# adv_timer.net
KiCad netlist of a schematic drawn in EAGLE
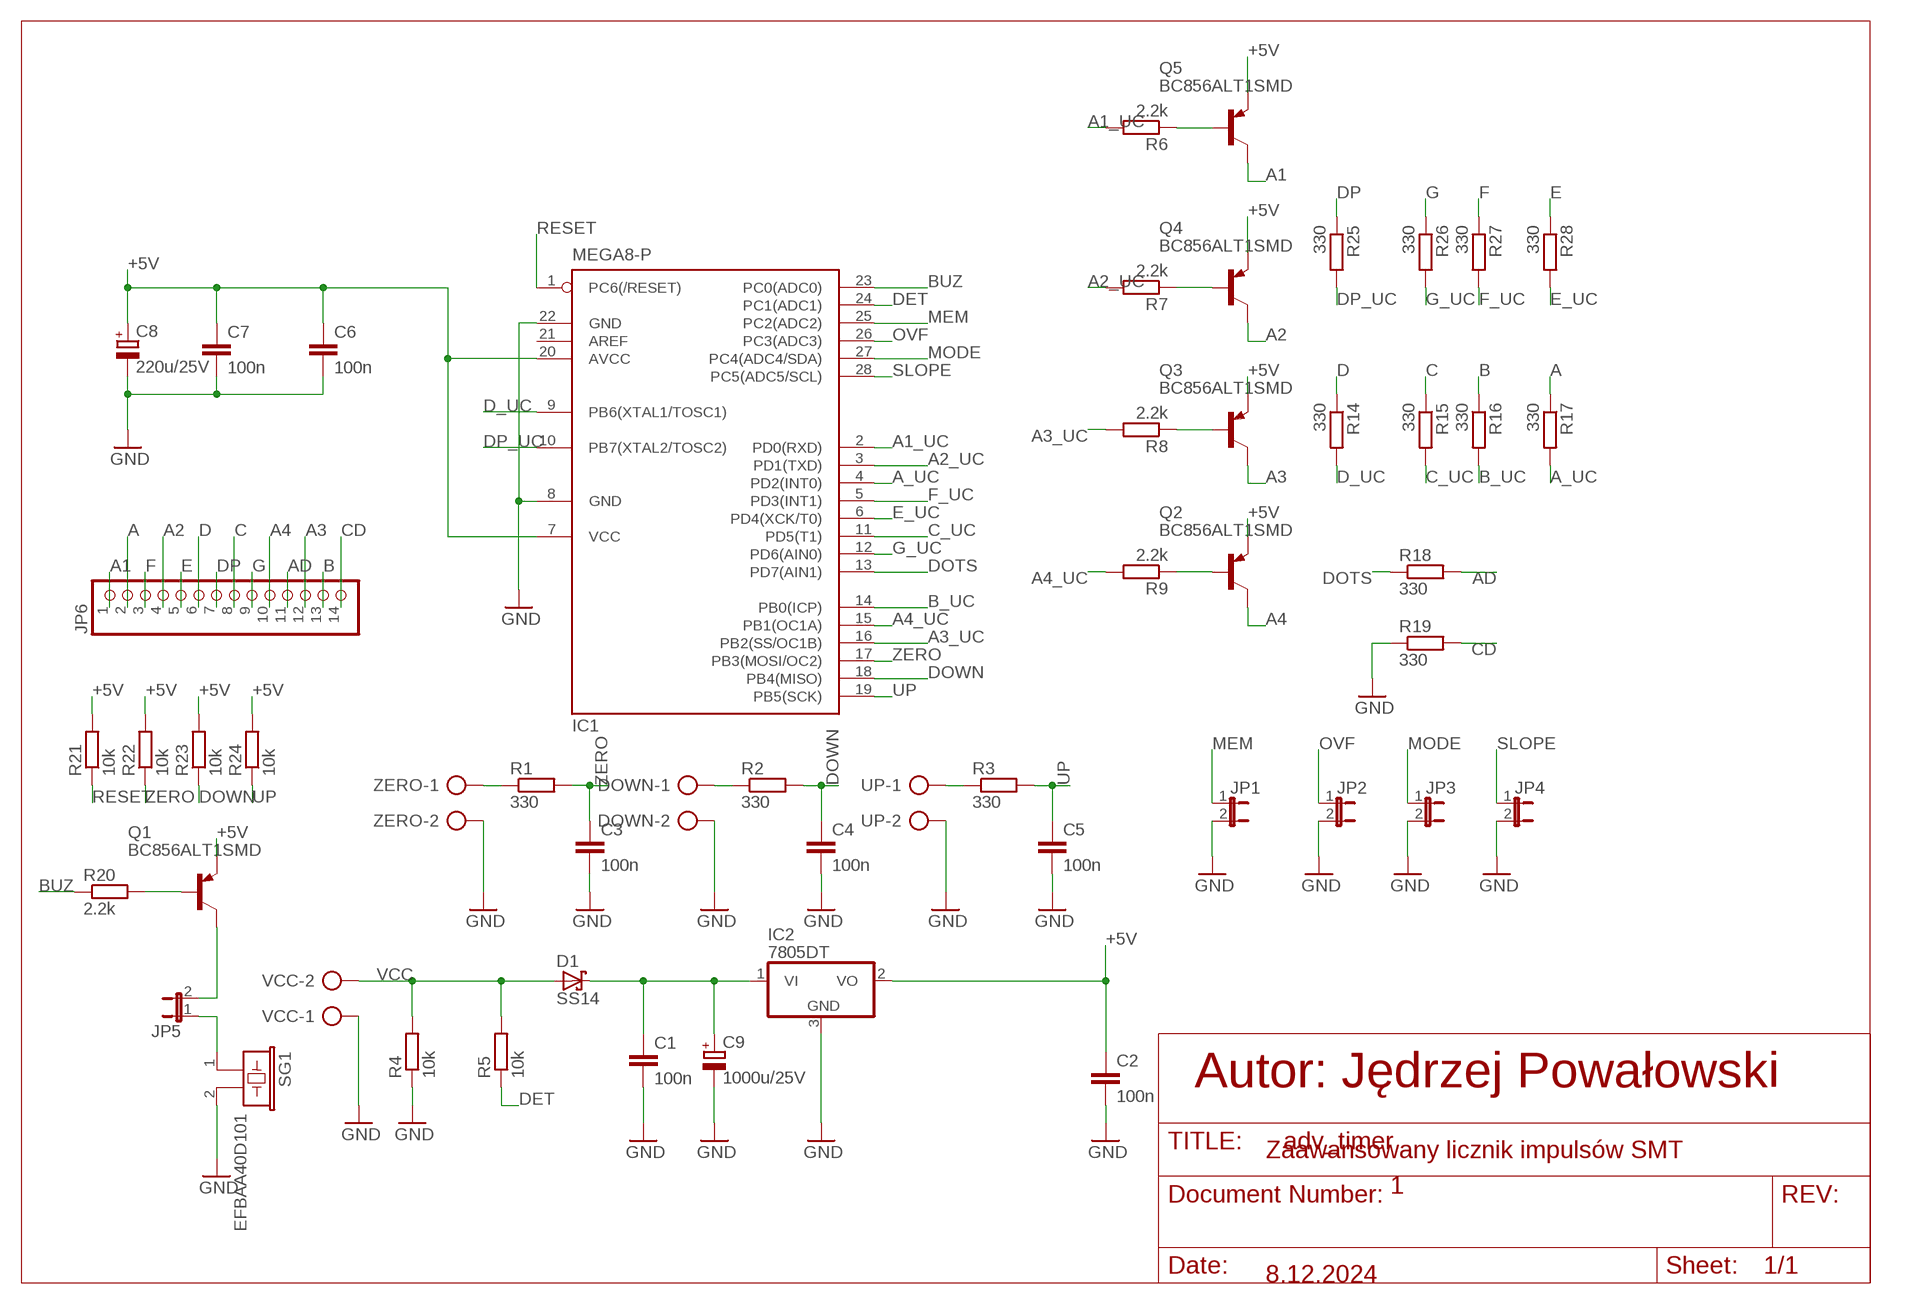
[diagram p0: schematic, sheet 1]

(export (version "E")
  (design (tool "Eeschema 10.0.6"))
  (components
    (comp (ref "C1")
      (value "100n")
      (footprint "eagle-import:C1210K")
      (libsource (lib "eagle-import") (part "C-EUC1210K"))
    )
    (comp (ref "C2")
      (value "100n")
      (footprint "eagle-import:C1210K")
      (libsource (lib "eagle-import") (part "C-EUC1210K"))
    )
    (comp (ref "C3")
      (value "100n")
      (footprint "eagle-import:C1210K")
      (libsource (lib "eagle-import") (part "C-EUC1210K"))
    )
    (comp (ref "C4")
      (value "100n")
      (footprint "eagle-import:C1210K")
      (libsource (lib "eagle-import") (part "C-EUC1210K"))
    )
    (comp (ref "C5")
      (value "100n")
      (footprint "eagle-import:C1210K")
      (libsource (lib "eagle-import") (part "C-EUC1210K"))
    )
    (comp (ref "C6")
      (value "100n")
      (footprint "eagle-import:C1210K")
      (libsource (lib "eagle-import") (part "C-EUC1210K"))
    )
    (comp (ref "C7")
      (value "100n")
      (footprint "eagle-import:C1210K")
      (libsource (lib "eagle-import") (part "C-EUC1210K"))
    )
    (comp (ref "C8")
      (value "220u/25V")
      (footprint "eagle-import:153CLV-0810")
      (libsource (lib "eagle-import") (part "CPOL-EU153CLV-0810"))
    )
    (comp (ref "C9")
      (value "1000u/25V")
      (footprint "eagle-import:153CLV-0810")
      (libsource (lib "eagle-import") (part "CPOL-EU153CLV-0810"))
    )
    (comp (ref "D1")
      (value "SS14")
      (footprint "eagle-import:DO-214AC")
      (fields (field (name "MF") "onsemi"))
      (libsource (lib "eagle-import") (part "SS14"))
    )
    (comp (ref "DOWN")
      (value "AK300/2")
      (footprint "eagle-import:AK300_2")
      (libsource (lib "eagle-import") (part "AK300/2"))
    )
    (comp (ref "IC1")
      (value "MEGA8-P")
      (footprint "eagle-import:DIL28-3")
      (libsource (lib "eagle-import") (part "MEGA8-P"))
    )
    (comp (ref "IC2")
      (value "7805DT")
      (footprint "eagle-import:TO252")
      (libsource (lib "eagle-import") (part "78DT05"))
    )
    (comp (ref "JP1")
      (value "JP1E")
      (footprint "eagle-import:JP1")
      (libsource (lib "eagle-import") (part "JP1E"))
    )
    (comp (ref "JP2")
      (value "JP1E")
      (footprint "eagle-import:JP1")
      (libsource (lib "eagle-import") (part "JP1E"))
    )
    (comp (ref "JP3")
      (value "JP1E")
      (footprint "eagle-import:JP1")
      (libsource (lib "eagle-import") (part "JP1E"))
    )
    (comp (ref "JP4")
      (value "JP1E")
      (footprint "eagle-import:JP1")
      (libsource (lib "eagle-import") (part "JP1E"))
    )
    (comp (ref "JP5")
      (value "JP1E")
      (footprint "eagle-import:JP1")
      (libsource (lib "eagle-import") (part "JP1E"))
    )
    (comp (ref "JP6")
      (value "PINHD-1X14/90")
      (footprint "eagle-import:1X14_90")
      (libsource (lib "eagle-import") (part "PINHD-1X14/90"))
    )
    (comp (ref "Q1")
      (value "BC856ALT1SMD")
      (footprint "eagle-import:SOT23-BEC")
      (libsource (lib "eagle-import") (part "BC856SMDALT1"))
    )
    (comp (ref "Q2")
      (value "BC856ALT1SMD")
      (footprint "eagle-import:SOT23-BEC")
      (libsource (lib "eagle-import") (part "BC856SMDALT1"))
    )
    (comp (ref "Q3")
      (value "BC856ALT1SMD")
      (footprint "eagle-import:SOT23-BEC")
      (libsource (lib "eagle-import") (part "BC856SMDALT1"))
    )
    (comp (ref "Q4")
      (value "BC856ALT1SMD")
      (footprint "eagle-import:SOT23-BEC")
      (libsource (lib "eagle-import") (part "BC856SMDALT1"))
    )
    (comp (ref "Q5")
      (value "BC856ALT1SMD")
      (footprint "eagle-import:SOT23-BEC")
      (libsource (lib "eagle-import") (part "BC856SMDALT1"))
    )
    (comp (ref "R1")
      (value "330")
      (footprint "eagle-import:M1206")
      (libsource (lib "eagle-import") (part "R-EU_M1206"))
    )
    (comp (ref "R2")
      (value "330")
      (footprint "eagle-import:M1206")
      (libsource (lib "eagle-import") (part "R-EU_M1206"))
    )
    (comp (ref "R3")
      (value "330")
      (footprint "eagle-import:M1206")
      (libsource (lib "eagle-import") (part "R-EU_M1206"))
    )
    (comp (ref "R4")
      (value "10k")
      (footprint "eagle-import:M1206")
      (libsource (lib "eagle-import") (part "R-EU_M1206"))
    )
    (comp (ref "R5")
      (value "10k")
      (footprint "eagle-import:M1206")
      (libsource (lib "eagle-import") (part "R-EU_M1206"))
    )
    (comp (ref "R6")
      (value "2.2k")
      (footprint "eagle-import:R0805")
      (libsource (lib "eagle-import") (part "R-EU_R0805"))
    )
    (comp (ref "R7")
      (value "2.2k")
      (footprint "eagle-import:R0805")
      (libsource (lib "eagle-import") (part "R-EU_R0805"))
    )
    (comp (ref "R8")
      (value "2.2k")
      (footprint "eagle-import:R0805")
      (libsource (lib "eagle-import") (part "R-EU_R0805"))
    )
    (comp (ref "R9")
      (value "2.2k")
      (footprint "eagle-import:R0805")
      (libsource (lib "eagle-import") (part "R-EU_R0805"))
    )
    (comp (ref "R14")
      (value "330")
      (footprint "eagle-import:R0805")
      (libsource (lib "eagle-import") (part "R-EU_R0805"))
    )
    (comp (ref "R15")
      (value "330")
      (footprint "eagle-import:R0805")
      (libsource (lib "eagle-import") (part "R-EU_R0805"))
    )
    (comp (ref "R16")
      (value "330")
      (footprint "eagle-import:R0805")
      (libsource (lib "eagle-import") (part "R-EU_R0805"))
    )
    (comp (ref "R17")
      (value "330")
      (footprint "eagle-import:R0805")
      (libsource (lib "eagle-import") (part "R-EU_R0805"))
    )
    (comp (ref "R18")
      (value "330")
      (footprint "eagle-import:R0805")
      (libsource (lib "eagle-import") (part "R-EU_R0805"))
    )
    (comp (ref "R19")
      (value "330")
      (footprint "eagle-import:R0805")
      (libsource (lib "eagle-import") (part "R-EU_R0805"))
    )
    (comp (ref "R20")
      (value "2.2k")
      (footprint "eagle-import:R0805")
      (libsource (lib "eagle-import") (part "R-EU_R0805"))
    )
    (comp (ref "R21")
      (value "10k")
      (footprint "eagle-import:R0805")
      (libsource (lib "eagle-import") (part "R-EU_R0805"))
    )
    (comp (ref "R22")
      (value "10k")
      (footprint "eagle-import:R0805")
      (libsource (lib "eagle-import") (part "R-EU_R0805"))
    )
    (comp (ref "R23")
      (value "10k")
      (footprint "eagle-import:R0805")
      (libsource (lib "eagle-import") (part "R-EU_R0805"))
    )
    (comp (ref "R24")
      (value "10k")
      (footprint "eagle-import:R0805")
      (libsource (lib "eagle-import") (part "R-EU_R0805"))
    )
    (comp (ref "R25")
      (value "330")
      (footprint "eagle-import:R0805")
      (libsource (lib "eagle-import") (part "R-EU_R0805"))
    )
    (comp (ref "R26")
      (value "330")
      (footprint "eagle-import:R0805")
      (libsource (lib "eagle-import") (part "R-EU_R0805"))
    )
    (comp (ref "R27")
      (value "330")
      (footprint "eagle-import:R0805")
      (libsource (lib "eagle-import") (part "R-EU_R0805"))
    )
    (comp (ref "R28")
      (value "330")
      (footprint "eagle-import:R0805")
      (libsource (lib "eagle-import") (part "R-EU_R0805"))
    )
    (comp (ref "SG1")
      (value "EFBAA40D101")
      (footprint "eagle-import:EFBAA40D101")
      (libsource (lib "eagle-import") (part "EFB?AA40D101"))
    )
    (comp (ref "UP")
      (value "AK300/2")
      (footprint "eagle-import:AK300_2")
      (libsource (lib "eagle-import") (part "AK300/2"))
    )
    (comp (ref "VCC")
      (value "AK300/2")
      (footprint "eagle-import:AK300_2")
      (libsource (lib "eagle-import") (part "AK300/2"))
    )
    (comp (ref "ZERO")
      (value "AK300/2")
      (footprint "eagle-import:AK300_2")
      (libsource (lib "eagle-import") (part "AK300/2"))
    )
  )
  (nets
    (net (code "1") (name "/+5V") (class "Default")
      (node (ref "C2") (pin "1") (pinfunction "1_1") (pintype "passive"))
      (node (ref "C6") (pin "1") (pinfunction "1_1") (pintype "passive"))
      (node (ref "C7") (pin "1") (pinfunction "1_1") (pintype "passive"))
      (node (ref "C8") (pin "+") (pinfunction "+_+") (pintype "passive"))
      (node (ref "IC1") (pin "20") (pinfunction "AVCC_20") (pintype "power_in"))
      (node (ref "IC1") (pin "7") (pinfunction "VCC_7") (pintype "power_in"))
      (node (ref "IC2") (pin "2") (pinfunction "VO_2") (pintype "passive"))
      (node (ref "Q1") (pin "E") (pinfunction "E_E") (pintype "passive"))
      (node (ref "Q2") (pin "E") (pinfunction "E_E") (pintype "passive"))
      (node (ref "Q3") (pin "E") (pinfunction "E_E") (pintype "passive"))
      (node (ref "Q4") (pin "E") (pinfunction "E_E") (pintype "passive"))
      (node (ref "Q5") (pin "E") (pinfunction "E_E") (pintype "passive"))
      (node (ref "R21") (pin "2") (pinfunction "2_2") (pintype "passive"))
      (node (ref "R22") (pin "2") (pinfunction "2_2") (pintype "passive"))
      (node (ref "R23") (pin "2") (pinfunction "2_2") (pintype "passive"))
      (node (ref "R24") (pin "2") (pinfunction "2_2") (pintype "passive"))
    )
    (net (code "2") (name "/A") (class "Default")
      (node (ref "JP6") (pin "2") (pinfunction "2_2") (pintype "passive"))
      (node (ref "R17") (pin "1") (pinfunction "1_1") (pintype "passive"))
    )
    (net (code "3") (name "/A1") (class "Default")
      (node (ref "JP6") (pin "1") (pinfunction "1_1") (pintype "passive"))
      (node (ref "Q5") (pin "C") (pinfunction "C_C") (pintype "passive"))
    )
    (net (code "4") (name "/A1_UC") (class "Default")
      (node (ref "IC1") (pin "2") (pinfunction "PD0(RXD)_2") (pintype "bidirectional"))
      (node (ref "R6") (pin "2") (pinfunction "2_2") (pintype "passive"))
    )
    (net (code "5") (name "/A2") (class "Default")
      (node (ref "JP6") (pin "4") (pinfunction "4_4") (pintype "passive"))
      (node (ref "Q4") (pin "C") (pinfunction "C_C") (pintype "passive"))
    )
    (net (code "6") (name "/A2_UC") (class "Default")
      (node (ref "IC1") (pin "3") (pinfunction "PD1(TXD)_3") (pintype "bidirectional"))
      (node (ref "R7") (pin "2") (pinfunction "2_2") (pintype "passive"))
    )
    (net (code "7") (name "/A3") (class "Default")
      (node (ref "JP6") (pin "12") (pinfunction "12_12") (pintype "passive"))
      (node (ref "Q3") (pin "C") (pinfunction "C_C") (pintype "passive"))
    )
    (net (code "8") (name "/A3_UC") (class "Default")
      (node (ref "IC1") (pin "16") (pinfunction "PB2(SS/OC1B)_16") (pintype "bidirectional"))
      (node (ref "R8") (pin "2") (pinfunction "2_2") (pintype "passive"))
    )
    (net (code "9") (name "/A4") (class "Default")
      (node (ref "JP6") (pin "10") (pinfunction "10_10") (pintype "passive"))
      (node (ref "Q2") (pin "C") (pinfunction "C_C") (pintype "passive"))
    )
    (net (code "10") (name "/A4_UC") (class "Default")
      (node (ref "IC1") (pin "15") (pinfunction "PB1(OC1A)_15") (pintype "bidirectional"))
      (node (ref "R9") (pin "2") (pinfunction "2_2") (pintype "passive"))
    )
    (net (code "11") (name "/AD") (class "Default")
      (node (ref "JP6") (pin "11") (pinfunction "11_11") (pintype "passive"))
      (node (ref "R18") (pin "2") (pinfunction "2_2") (pintype "passive"))
    )
    (net (code "12") (name "/A_UC") (class "Default")
      (node (ref "IC1") (pin "4") (pinfunction "PD2(INT0)_4") (pintype "bidirectional"))
      (node (ref "R17") (pin "2") (pinfunction "2_2") (pintype "passive"))
    )
    (net (code "13") (name "/B") (class "Default")
      (node (ref "JP6") (pin "13") (pinfunction "13_13") (pintype "passive"))
      (node (ref "R16") (pin "1") (pinfunction "1_1") (pintype "passive"))
    )
    (net (code "14") (name "/BUZ") (class "Default")
      (node (ref "IC1") (pin "23") (pinfunction "PC0(ADC0)_23") (pintype "bidirectional"))
      (node (ref "R20") (pin "1") (pinfunction "1_1") (pintype "passive"))
    )
    (net (code "15") (name "/B_UC") (class "Default")
      (node (ref "IC1") (pin "14") (pinfunction "PB0(ICP)_14") (pintype "bidirectional"))
      (node (ref "R16") (pin "2") (pinfunction "2_2") (pintype "passive"))
    )
    (net (code "16") (name "/C") (class "Default")
      (node (ref "JP6") (pin "8") (pinfunction "8_8") (pintype "passive"))
      (node (ref "R15") (pin "1") (pinfunction "1_1") (pintype "passive"))
    )
    (net (code "17") (name "/CD") (class "Default")
      (node (ref "JP6") (pin "14") (pinfunction "14_14") (pintype "passive"))
      (node (ref "R19") (pin "2") (pinfunction "2_2") (pintype "passive"))
    )
    (net (code "18") (name "/C_UC") (class "Default")
      (node (ref "IC1") (pin "11") (pinfunction "PD5(T1)_11") (pintype "bidirectional"))
      (node (ref "R15") (pin "2") (pinfunction "2_2") (pintype "passive"))
    )
    (net (code "19") (name "/D") (class "Default")
      (node (ref "JP6") (pin "6") (pinfunction "6_6") (pintype "passive"))
      (node (ref "R14") (pin "1") (pinfunction "1_1") (pintype "passive"))
    )
    (net (code "20") (name "/DET") (class "Default")
      (node (ref "IC1") (pin "24") (pinfunction "PC1(ADC1)_24") (pintype "bidirectional"))
      (node (ref "R5") (pin "1") (pinfunction "1_1") (pintype "passive"))
    )
    (net (code "21") (name "/DOTS") (class "Default")
      (node (ref "IC1") (pin "13") (pinfunction "PD7(AIN1)_13") (pintype "bidirectional"))
      (node (ref "R18") (pin "1") (pinfunction "1_1") (pintype "passive"))
    )
    (net (code "22") (name "/DOWN") (class "Default")
      (node (ref "C4") (pin "1") (pinfunction "1_1") (pintype "passive"))
      (node (ref "IC1") (pin "18") (pinfunction "PB4(MISO)_18") (pintype "bidirectional"))
      (node (ref "R2") (pin "2") (pinfunction "2_2") (pintype "passive"))
      (node (ref "R23") (pin "1") (pinfunction "1_1") (pintype "passive"))
    )
    (net (code "23") (name "/DP") (class "Default")
      (node (ref "JP6") (pin "7") (pinfunction "7_7") (pintype "passive"))
      (node (ref "R25") (pin "1") (pinfunction "1_1") (pintype "passive"))
    )
    (net (code "24") (name "/DP_UC") (class "Default")
      (node (ref "IC1") (pin "10") (pinfunction "PB7(XTAL2/TOSC2)_10") (pintype "bidirectional"))
      (node (ref "R25") (pin "2") (pinfunction "2_2") (pintype "passive"))
    )
    (net (code "25") (name "/D_UC") (class "Default")
      (node (ref "IC1") (pin "9") (pinfunction "PB6(XTAL1/TOSC1)_9") (pintype "bidirectional"))
      (node (ref "R14") (pin "2") (pinfunction "2_2") (pintype "passive"))
    )
    (net (code "26") (name "/E") (class "Default")
      (node (ref "JP6") (pin "5") (pinfunction "5_5") (pintype "passive"))
      (node (ref "R28") (pin "1") (pinfunction "1_1") (pintype "passive"))
    )
    (net (code "27") (name "/E_UC") (class "Default")
      (node (ref "IC1") (pin "6") (pinfunction "PD4(XCK/T0)_6") (pintype "bidirectional"))
      (node (ref "R28") (pin "2") (pinfunction "2_2") (pintype "passive"))
    )
    (net (code "28") (name "/F") (class "Default")
      (node (ref "JP6") (pin "3") (pinfunction "3_3") (pintype "passive"))
      (node (ref "R27") (pin "1") (pinfunction "1_1") (pintype "passive"))
    )
    (net (code "29") (name "/F_UC") (class "Default")
      (node (ref "IC1") (pin "5") (pinfunction "PD3(INT1)_5") (pintype "bidirectional"))
      (node (ref "R27") (pin "2") (pinfunction "2_2") (pintype "passive"))
    )
    (net (code "30") (name "/G") (class "Default")
      (node (ref "JP6") (pin "9") (pinfunction "9_9") (pintype "passive"))
      (node (ref "R26") (pin "1") (pinfunction "1_1") (pintype "passive"))
    )
    (net (code "31") (name "/G_UC") (class "Default")
      (node (ref "IC1") (pin "12") (pinfunction "PD6(AIN0)_12") (pintype "bidirectional"))
      (node (ref "R26") (pin "2") (pinfunction "2_2") (pintype "passive"))
    )
    (net (code "32") (name "/MEM") (class "Default")
      (node (ref "IC1") (pin "25") (pinfunction "PC2(ADC2)_25") (pintype "bidirectional"))
      (node (ref "JP1") (pin "1") (pinfunction "1_1") (pintype "passive"))
    )
    (net (code "33") (name "/MODE") (class "Default")
      (node (ref "IC1") (pin "27") (pinfunction "PC4(ADC4/SDA)_27") (pintype "bidirectional"))
      (node (ref "JP3") (pin "1") (pinfunction "1_1") (pintype "passive"))
    )
    (net (code "34") (name "/OVF") (class "Default")
      (node (ref "IC1") (pin "26") (pinfunction "PC3(ADC3)_26") (pintype "bidirectional"))
      (node (ref "JP2") (pin "1") (pinfunction "1_1") (pintype "passive"))
    )
    (net (code "35") (name "/RESET") (class "Default")
      (node (ref "IC1") (pin "1") (pinfunction "PC6(/RESET)_1") (pintype "bidirectional"))
      (node (ref "R21") (pin "1") (pinfunction "1_1") (pintype "passive"))
    )
    (net (code "36") (name "/SLOPE") (class "Default")
      (node (ref "IC1") (pin "28") (pinfunction "PC5(ADC5/SCL)_28") (pintype "bidirectional"))
      (node (ref "JP4") (pin "1") (pinfunction "1_1") (pintype "passive"))
    )
    (net (code "37") (name "/UP") (class "Default")
      (node (ref "C5") (pin "1") (pinfunction "1_1") (pintype "passive"))
      (node (ref "IC1") (pin "19") (pinfunction "PB5(SCK)_19") (pintype "bidirectional"))
      (node (ref "R24") (pin "1") (pinfunction "1_1") (pintype "passive"))
      (node (ref "R3") (pin "2") (pinfunction "2_2") (pintype "passive"))
    )
    (net (code "38") (name "/VCC") (class "Default")
      (node (ref "D1") (pin "A") (pinfunction "A_A") (pintype "passive"))
      (node (ref "R4") (pin "2") (pinfunction "2_2") (pintype "passive"))
      (node (ref "R5") (pin "2") (pinfunction "2_2") (pintype "passive"))
      (node (ref "VCC") (pin "2") (pinfunction "KL_2") (pintype "passive"))
    )
    (net (code "39") (name "/ZERO") (class "Default")
      (node (ref "C3") (pin "1") (pinfunction "1_1") (pintype "passive"))
      (node (ref "IC1") (pin "17") (pinfunction "PB3(MOSI/OC2)_17") (pintype "bidirectional"))
      (node (ref "R1") (pin "2") (pinfunction "2_2") (pintype "passive"))
      (node (ref "R22") (pin "1") (pinfunction "1_1") (pintype "passive"))
    )
    (net (code "40") (name "GND") (class "Default")
      (node (ref "C1") (pin "2") (pinfunction "2_2") (pintype "passive"))
      (node (ref "C2") (pin "2") (pinfunction "2_2") (pintype "passive"))
      (node (ref "C3") (pin "2") (pinfunction "2_2") (pintype "passive"))
      (node (ref "C4") (pin "2") (pinfunction "2_2") (pintype "passive"))
      (node (ref "C5") (pin "2") (pinfunction "2_2") (pintype "passive"))
      (node (ref "C6") (pin "2") (pinfunction "2_2") (pintype "passive"))
      (node (ref "C7") (pin "2") (pinfunction "2_2") (pintype "passive"))
      (node (ref "C8") (pin "-") (pinfunction "-_-") (pintype "passive"))
      (node (ref "C9") (pin "-") (pinfunction "-_-") (pintype "passive"))
      (node (ref "DOWN") (pin "2") (pinfunction "KL_2") (pintype "passive"))
      (node (ref "IC1") (pin "22") (pinfunction "GND_22") (pintype "power_in"))
      (node (ref "IC1") (pin "8") (pinfunction "GND_8") (pintype "power_in"))
      (node (ref "IC2") (pin "3") (pinfunction "GND_3") (pintype "passive"))
      (node (ref "JP1") (pin "2") (pinfunction "2_2") (pintype "passive"))
      (node (ref "JP2") (pin "2") (pinfunction "2_2") (pintype "passive"))
      (node (ref "JP3") (pin "2") (pinfunction "2_2") (pintype "passive"))
      (node (ref "JP4") (pin "2") (pinfunction "2_2") (pintype "passive"))
      (node (ref "R19") (pin "1") (pinfunction "1_1") (pintype "passive"))
      (node (ref "R4") (pin "1") (pinfunction "1_1") (pintype "passive"))
      (node (ref "SG1") (pin "2") (pinfunction "2_2") (pintype "passive"))
      (node (ref "UP") (pin "2") (pinfunction "KL_2") (pintype "passive"))
      (node (ref "VCC") (pin "1") (pinfunction "KL_1") (pintype "passive"))
      (node (ref "ZERO") (pin "2") (pinfunction "KL_2") (pintype "passive"))
    )
    (net (code "41") (name "Net-(DOWNA-KL)") (class "Default")
      (node (ref "DOWN") (pin "1") (pinfunction "KL_1") (pintype "passive"))
      (node (ref "R2") (pin "1") (pinfunction "1_1") (pintype "passive"))
    )
    (net (code "42") (name "Net-(IC2-VI)") (class "Default")
      (node (ref "C1") (pin "1") (pinfunction "1_1") (pintype "passive"))
      (node (ref "C9") (pin "+") (pinfunction "+_+") (pintype "passive"))
      (node (ref "D1") (pin "K") (pinfunction "K_K") (pintype "passive"))
      (node (ref "IC2") (pin "1") (pinfunction "VI_1") (pintype "input"))
    )
    (net (code "43") (name "Net-(JP5-Pad1)") (class "Default")
      (node (ref "JP5") (pin "1") (pinfunction "1_1") (pintype "passive"))
      (node (ref "SG1") (pin "1") (pinfunction "1_1") (pintype "passive"))
    )
    (net (code "44") (name "Net-(JP5-Pad2)") (class "Default")
      (node (ref "JP5") (pin "2") (pinfunction "2_2") (pintype "passive"))
      (node (ref "Q1") (pin "C") (pinfunction "C_C") (pintype "passive"))
    )
    (net (code "45") (name "Net-(Q1-PadB)") (class "Default")
      (node (ref "Q1") (pin "B") (pinfunction "B_B") (pintype "passive"))
      (node (ref "R20") (pin "2") (pinfunction "2_2") (pintype "passive"))
    )
    (net (code "46") (name "Net-(Q2-PadB)") (class "Default")
      (node (ref "Q2") (pin "B") (pinfunction "B_B") (pintype "passive"))
      (node (ref "R9") (pin "1") (pinfunction "1_1") (pintype "passive"))
    )
    (net (code "47") (name "Net-(Q3-PadB)") (class "Default")
      (node (ref "Q3") (pin "B") (pinfunction "B_B") (pintype "passive"))
      (node (ref "R8") (pin "1") (pinfunction "1_1") (pintype "passive"))
    )
    (net (code "48") (name "Net-(Q4-PadB)") (class "Default")
      (node (ref "Q4") (pin "B") (pinfunction "B_B") (pintype "passive"))
      (node (ref "R7") (pin "1") (pinfunction "1_1") (pintype "passive"))
    )
    (net (code "49") (name "Net-(Q5-PadB)") (class "Default")
      (node (ref "Q5") (pin "B") (pinfunction "B_B") (pintype "passive"))
      (node (ref "R6") (pin "1") (pinfunction "1_1") (pintype "passive"))
    )
    (net (code "50") (name "Net-(UPA-KL)") (class "Default")
      (node (ref "R3") (pin "1") (pinfunction "1_1") (pintype "passive"))
      (node (ref "UP") (pin "1") (pinfunction "KL_1") (pintype "passive"))
    )
    (net (code "51") (name "Net-(ZEROA-KL)") (class "Default")
      (node (ref "R1") (pin "1") (pinfunction "1_1") (pintype "passive"))
      (node (ref "ZERO") (pin "1") (pinfunction "KL_1") (pintype "passive"))
    )
    (net (code "52") (name "unconnected-(IC1-AREF-Pad21)") (class "Default")
      (node (ref "IC1") (pin "21") (pinfunction "AREF_21") (pintype "passive"))
    )
  )
)
